# sensor.net
KiCad netlist of a schematic drawn in Altium Designer
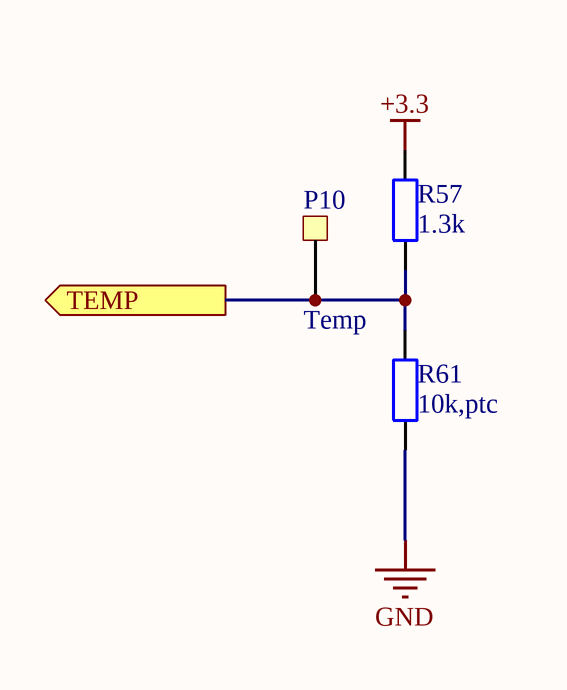
[diagram p0: sensor.SchDoc]

(export (version "E")
  (design (tool "Eeschema 10.0.6"))
  (components
    (comp (ref "P10")
      (value "Temp")
      (footprint "Pad_3x3mm")
      (description "Single Pad or Testpoint")
      (libsource (lib "IDSC std connectors") (part "Pad"))
    )
    (comp (ref "R57")
      (value "1.3k")
      (footprint "RES_0603i_1608m -N")
      (description "Resistor")
      (libsource (lib "IDSC std generic parts") (part "Res"))
    )
    (comp (ref "R61")
      (value "10k,ptc")
      (footprint "RES_0402i_1005m -N")
      (description "temp sensor, ptc\r\n10k")
      (libsource (lib "") (part "Res_1"))
    )
  )
  (nets
    (net (code "1") (name "+3.3") (class "Default")
      (node (ref "R57") (pin "1") (pinfunction "1_1") (pintype "passive"))
    )
    (net (code "2") (name "/TEMP") (class "Default")
      (node (ref "P10") (pin "1") (pinfunction "1_1") (pintype "passive"))
      (node (ref "R57") (pin "2") (pinfunction "2_2") (pintype "passive"))
      (node (ref "R61") (pin "2") (pinfunction "2_2") (pintype "passive"))
    )
    (net (code "3") (name "GND") (class "Default")
      (node (ref "R61") (pin "1") (pinfunction "1_1") (pintype "passive"))
    )
  )
)
